# DAQ_Schematic_V1.net
KiCad netlist of a schematic drawn in Altium Designer
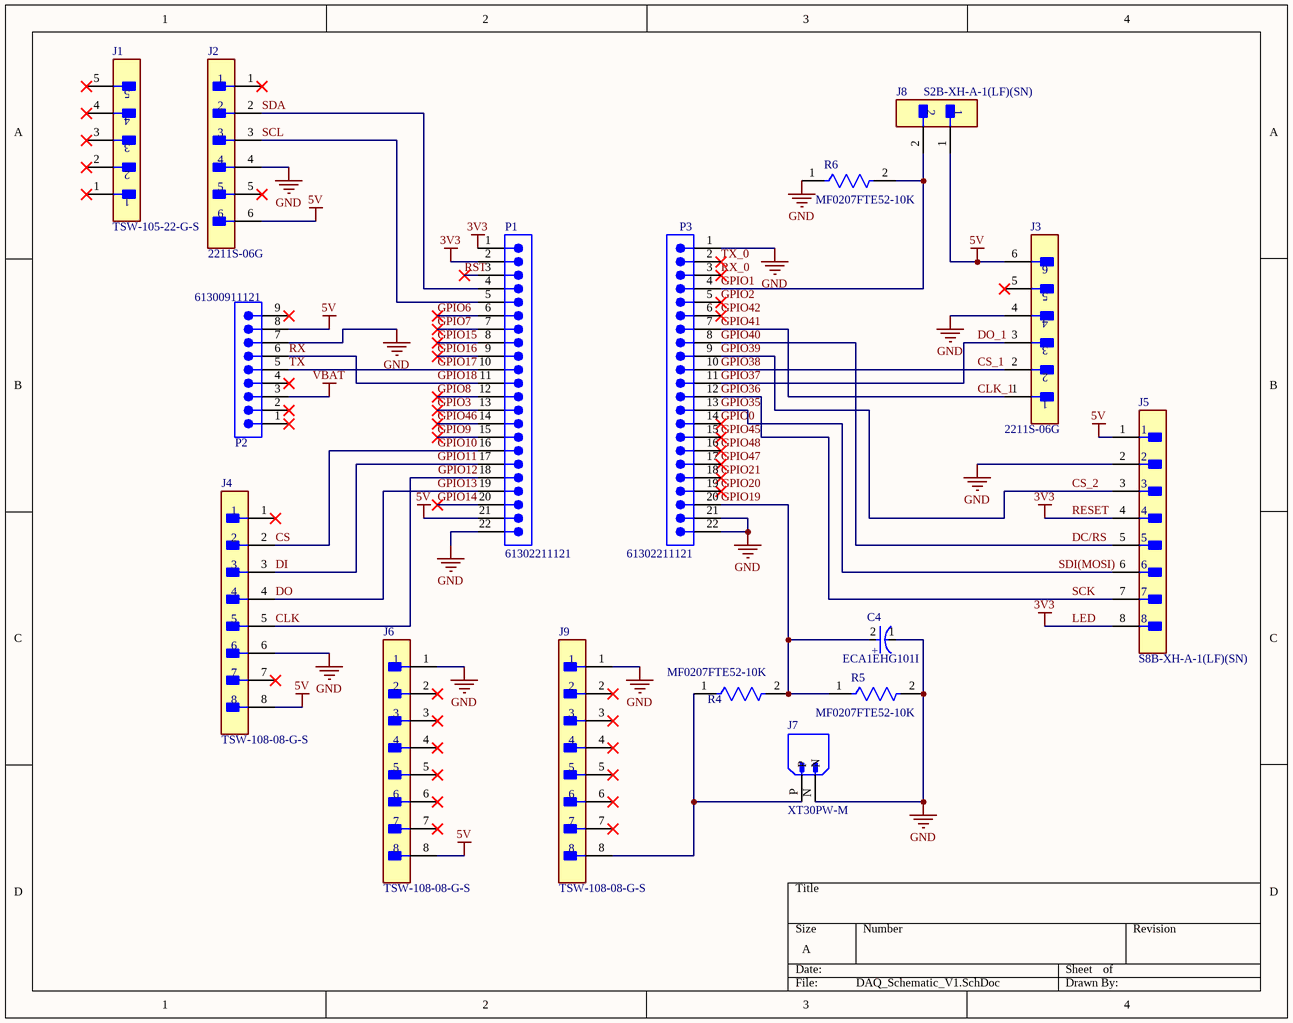
[diagram p0: DAQ_Schematic_V1.SchDoc]

(export (version "E")
  (design (tool "Eeschema 10.0.6"))
  (components
    (comp (ref "C4")
      (value "ECA1EHG101I")
      (footprint "FP-RAD-TH-D_6_3_0_5-L_11-MFG")
      (description "Aluminum Electrolytic Capacitors (Radial Lead Type) AEC-Q200 Qualified 100uF ±20% 25V")
      (fields (field (name "TOLERANCE") "20%"))
      (libsource (lib "Altium Content Vault") (part "203bc49f2ac43e59fd269a8c329ed05"))
    )
    (comp (ref "J1")
      (value "TSW-105-22-G-S")
      (footprint "FP-TSW-105-22-G-S-MFG")
      (description "CONN HEADER VERT 5POS 2.54MM")
      (libsource (lib "Altium Content Vault") (part "bf93c07fd2649a848d0ec8585582aab"))
    )
    (comp (ref "J2")
      (value "2211S-06G")
      (footprint "FP-2211S-06G-MFG")
      (description "Board-To-Board Connector, 2.54 mm, 6 Contacts, Header, 2211S Series, Through Hole, 1 Rows")
      (libsource (lib "") (part "f2cb566baf1c37ab5a3b8e90bbeafd6_1"))
    )
    (comp (ref "J3")
      (value "2211S-06G")
      (footprint "FP-2211S-06G-MFG")
      (description "Board-To-Board Connector, 2.54 mm, 6 Contacts, Header, 2211S Series, Through Hole, 1 Rows")
      (libsource (lib "Altium Content Vault") (part "f2cb566baf1c37ab5a3b8e90bbeafd6"))
    )
    (comp (ref "J4")
      (value "TSW-108-08-G-S")
      (footprint "FP-TSW-108-08-G-S-MFG")
      (description "CONN HEADER VERT 8POS 2.54MM")
      (fields
        (field (name "MANUFACTURER") "Samtec")
        (field (name "OCTOPART") "https://octopart.com/tsw-108-08-g-s-samtec-272653")
      )
      (libsource (lib "") (part "99ec2b232beb5d2356d4d77f6a047f0_1"))
    )
    (comp (ref "J5")
      (value "S8B-XH-A-1(LF)(SN)")
      (footprint "FP-S8B-XH-A-1_LF_SN-MFG")
      (description "CONN HEADER R/A 8POS 2.5MM")
      (libsource (lib "Altium Content Vault") (part "99ec2b232beb5d2356d4d77f6a047f0"))
    )
    (comp (ref "J6")
      (value "TSW-108-08-G-S")
      (footprint "FP-TSW-108-08-G-S-MFG")
      (description "CONN HEADER VERT 8POS 2.54MM")
      (fields
        (field (name "MANUFACTURER") "Samtec")
        (field (name "OCTOPART") "https://octopart.com/tsw-108-08-g-s-samtec-272653")
      )
      (libsource (lib "") (part "99ec2b232beb5d2356d4d77f6a047f0_1"))
    )
    (comp (ref "J7")
      (value "XT30PW-M")
      (footprint "AMASS_XT30PW-M")
      (description "Socket; DC supply; XT30; male; PIN: 2; on PCBs; THT; Colour: yellow")
      (fields (field (name "MF") "AMASS"))
      (libsource (lib "ECE 282 PCB Designs") (part "XT30PW-M"))
    )
    (comp (ref "J8")
      (value "S2B-XH-A-1(LF)(SN)")
      (footprint "FP-S2B-XH-A-1_LF_SN-MFG")
      (description "CONN HEADER R/A 2POS 2.5MM")
      (libsource (lib "Altium Content Vault") (part "3bc925449376181038e59eaffc5286c"))
    )
    (comp (ref "J9")
      (value "TSW-108-08-G-S")
      (footprint "FP-TSW-108-08-G-S-MFG")
      (description "CONN HEADER VERT 8POS 2.54MM")
      (fields
        (field (name "MANUFACTURER") "Samtec")
        (field (name "OCTOPART") "https://octopart.com/tsw-108-08-g-s-samtec-272653")
      )
      (libsource (lib "") (part "99ec2b232beb5d2356d4d77f6a047f0_1"))
    )
    (comp (ref "P1")
      (value "61302211121")
      (footprint "61302211121")
      (description "THT Vertical Pin Header WR-PHD, Pitch 2.54 mm, Single Row, 22 pins")
      (libsource (lib "Altium Content Vault") (part "Header_Male_1R_22P"))
    )
    (comp (ref "P2")
      (value "61300911121")
      (footprint "61300911121")
      (description "THT Vertical Pin Header WR-PHD, Pitch 2.54 mm, Single Row, 9 pins")
      (libsource (lib "Altium Content Vault") (part "Header_Male_1R_09P"))
    )
    (comp (ref "P3")
      (value "61302211121")
      (footprint "61302211121")
      (description "THT Vertical Pin Header WR-PHD, Pitch 2.54 mm, Single Row, 22 pins")
      (libsource (lib "Altium Content Vault") (part "Header_Male_1R_22P"))
    )
    (comp (ref "R4")
      (value "MF0207FTE52-10K")
      (footprint "FP-MF0207-MFG")
      (description "RES 10K OHM 1% 0.6W AXIAL")
      (fields (field (name "TOLERANCE") "1%"))
      (libsource (lib "Altium Content Vault") (part "1029c3af85768c4190bb7ad29bc67b5"))
    )
    (comp (ref "R5")
      (value "MF0207FTE52-10K")
      (footprint "FP-MF0207-MFG")
      (description "RES 10K OHM 1% 0.6W AXIAL")
      (fields (field (name "TOLERANCE") "1%"))
      (libsource (lib "Altium Content Vault") (part "1029c3af85768c4190bb7ad29bc67b5"))
    )
    (comp (ref "R6")
      (value "MF0207FTE52-10K")
      (footprint "FP-MF0207-MFG")
      (description "RES 10K OHM 1% 0.6W AXIAL")
      (fields (field (name "TOLERANCE") "1%"))
      (libsource (lib "Altium Content Vault") (part "1029c3af85768c4190bb7ad29bc67b5"))
    )
  )
  (nets
    (net (code "1") (name "/CLK") (class "Default")
      (node (ref "J4") (pin "5") (pinfunction "5_5") (pintype "passive"))
      (node (ref "P1") (pin "18") (pinfunction "18_18") (pintype "passive"))
    )
    (net (code "2") (name "/CLK_1") (class "Default")
      (node (ref "J3") (pin "1") (pinfunction "1_1") (pintype "passive"))
      (node (ref "P3") (pin "7") (pinfunction "7_7") (pintype "passive"))
    )
    (net (code "3") (name "/CS") (class "Default")
      (node (ref "J4") (pin "2") (pinfunction "2_2") (pintype "passive"))
      (node (ref "P1") (pin "16") (pinfunction "16_16") (pintype "passive"))
    )
    (net (code "4") (name "/CS_1") (class "Default")
      (node (ref "J3") (pin "2") (pinfunction "2_2") (pintype "passive"))
      (node (ref "P3") (pin "10") (pinfunction "10_10") (pintype "passive"))
    )
    (net (code "5") (name "/CS_2") (class "Default")
      (node (ref "J5") (pin "3") (pinfunction "3_3") (pintype "passive"))
      (node (ref "P3") (pin "9") (pinfunction "9_9") (pintype "passive"))
    )
    (net (code "6") (name "/DC{slash}RS") (class "Default")
      (node (ref "J5") (pin "5") (pinfunction "5_5") (pintype "passive"))
      (node (ref "P3") (pin "8") (pinfunction "8_8") (pintype "passive"))
    )
    (net (code "7") (name "/DI") (class "Default")
      (node (ref "J4") (pin "3") (pinfunction "3_3") (pintype "passive"))
      (node (ref "P1") (pin "17") (pinfunction "17_17") (pintype "passive"))
    )
    (net (code "8") (name "/DO") (class "Default")
      (node (ref "J4") (pin "4") (pinfunction "4_4") (pintype "passive"))
      (node (ref "P1") (pin "19") (pinfunction "19_19") (pintype "passive"))
    )
    (net (code "9") (name "/DO_1") (class "Default")
      (node (ref "J3") (pin "3") (pinfunction "3_3") (pintype "passive"))
      (node (ref "P3") (pin "11") (pinfunction "11_11") (pintype "passive"))
    )
    (net (code "10") (name "/GPIO0") (class "Default")
      (node (ref "P3") (pin "14") (pinfunction "14_14") (pintype "passive+no_connect"))
    )
    (net (code "11") (name "/GPIO1") (class "Default")
      (node (ref "J8") (pin "2") (pinfunction "2_2") (pintype "passive"))
      (node (ref "P3") (pin "4") (pinfunction "4_4") (pintype "passive"))
      (node (ref "R6") (pin "2") (pinfunction "2_2") (pintype "passive"))
    )
    (net (code "12") (name "/GPIO2") (class "Default")
      (node (ref "P3") (pin "5") (pinfunction "5_5") (pintype "passive+no_connect"))
    )
    (net (code "13") (name "/GPIO3") (class "Default")
      (node (ref "P1") (pin "13") (pinfunction "13_13") (pintype "passive+no_connect"))
    )
    (net (code "14") (name "/GPIO6") (class "Default")
      (node (ref "P1") (pin "6") (pinfunction "6_6") (pintype "passive+no_connect"))
    )
    (net (code "15") (name "/GPIO7") (class "Default")
      (node (ref "P1") (pin "7") (pinfunction "7_7") (pintype "passive+no_connect"))
    )
    (net (code "16") (name "/GPIO8") (class "Default")
      (node (ref "P1") (pin "12") (pinfunction "12_12") (pintype "passive+no_connect"))
    )
    (net (code "17") (name "/GPIO9") (class "Default")
      (node (ref "P1") (pin "15") (pinfunction "15_15") (pintype "passive+no_connect"))
    )
    (net (code "18") (name "/GPIO14") (class "Default")
      (node (ref "P1") (pin "20") (pinfunction "20_20") (pintype "passive+no_connect"))
    )
    (net (code "19") (name "/GPIO15") (class "Default")
      (node (ref "P1") (pin "8") (pinfunction "8_8") (pintype "passive+no_connect"))
    )
    (net (code "20") (name "/GPIO16") (class "Default")
      (node (ref "P1") (pin "9") (pinfunction "9_9") (pintype "passive+no_connect"))
    )
    (net (code "21") (name "/GPIO17") (class "Default")
      (node (ref "P1") (pin "10") (pinfunction "10_10") (pintype "passive"))
      (node (ref "P2") (pin "5") (pinfunction "5_5") (pintype "passive"))
    )
    (net (code "22") (name "/GPIO18") (class "Default")
      (node (ref "P1") (pin "11") (pinfunction "11_11") (pintype "passive"))
      (node (ref "P2") (pin "6") (pinfunction "6_6") (pintype "passive"))
    )
    (net (code "23") (name "/GPIO19") (class "Default")
      (node (ref "C4") (pin "2") (pinfunction "A_2") (pintype "passive"))
      (node (ref "P3") (pin "20") (pinfunction "20_20") (pintype "passive"))
      (node (ref "R4") (pin "2") (pinfunction "2_2") (pintype "passive"))
      (node (ref "R5") (pin "1") (pinfunction "1_1") (pintype "passive"))
    )
    (net (code "24") (name "/GPIO20") (class "Default")
      (node (ref "P3") (pin "19") (pinfunction "19_19") (pintype "passive+no_connect"))
    )
    (net (code "25") (name "/GPIO21") (class "Default")
      (node (ref "P3") (pin "18") (pinfunction "18_18") (pintype "passive+no_connect"))
    )
    (net (code "26") (name "/GPIO35") (class "Default")
      (node (ref "J5") (pin "6") (pinfunction "6_6") (pintype "passive"))
      (node (ref "P3") (pin "13") (pinfunction "13_13") (pintype "passive"))
    )
    (net (code "27") (name "/GPIO36") (class "Default")
      (node (ref "J5") (pin "7") (pinfunction "7_7") (pintype "passive"))
      (node (ref "P3") (pin "12") (pinfunction "12_12") (pintype "passive"))
    )
    (net (code "28") (name "/GPIO42") (class "Default")
      (node (ref "P3") (pin "6") (pinfunction "6_6") (pintype "passive+no_connect"))
    )
    (net (code "29") (name "/GPIO45") (class "Default")
      (node (ref "P3") (pin "15") (pinfunction "15_15") (pintype "passive+no_connect"))
    )
    (net (code "30") (name "/GPIO46") (class "Default")
      (node (ref "P1") (pin "14") (pinfunction "14_14") (pintype "passive+no_connect"))
    )
    (net (code "31") (name "/GPIO47") (class "Default")
      (node (ref "P3") (pin "17") (pinfunction "17_17") (pintype "passive+no_connect"))
    )
    (net (code "32") (name "/GPIO48") (class "Default")
      (node (ref "P3") (pin "16") (pinfunction "16_16") (pintype "passive+no_connect"))
    )
    (net (code "33") (name "/RST") (class "Default")
      (node (ref "P1") (pin "3") (pinfunction "3_3") (pintype "passive+no_connect"))
    )
    (net (code "34") (name "/RX_0") (class "Default")
      (node (ref "P3") (pin "3") (pinfunction "3_3") (pintype "passive+no_connect"))
    )
    (net (code "35") (name "/SCL") (class "Default")
      (node (ref "J2") (pin "3") (pinfunction "3_3") (pintype "passive"))
      (node (ref "P1") (pin "5") (pinfunction "5_5") (pintype "passive"))
    )
    (net (code "36") (name "/SDA") (class "Default")
      (node (ref "J2") (pin "2") (pinfunction "2_2") (pintype "passive"))
      (node (ref "P1") (pin "4") (pinfunction "4_4") (pintype "passive"))
    )
    (net (code "37") (name "/TX_0") (class "Default")
      (node (ref "P3") (pin "2") (pinfunction "2_2") (pintype "passive+no_connect"))
    )
    (net (code "38") (name "3V3") (class "Default")
      (node (ref "J5") (pin "4") (pinfunction "4_4") (pintype "passive"))
      (node (ref "J5") (pin "8") (pinfunction "8_8") (pintype "passive"))
      (node (ref "P1") (pin "1") (pinfunction "1_1") (pintype "passive"))
      (node (ref "P1") (pin "2") (pinfunction "2_2") (pintype "passive"))
    )
    (net (code "39") (name "5V") (class "Default")
      (node (ref "J2") (pin "6") (pinfunction "6_6") (pintype "passive"))
      (node (ref "J3") (pin "6") (pinfunction "6_6") (pintype "passive"))
      (node (ref "J4") (pin "8") (pinfunction "8_8") (pintype "passive"))
      (node (ref "J5") (pin "1") (pinfunction "1_1") (pintype "passive"))
      (node (ref "J6") (pin "8") (pinfunction "8_8") (pintype "passive"))
      (node (ref "J8") (pin "1") (pinfunction "1_1") (pintype "passive"))
      (node (ref "P1") (pin "21") (pinfunction "21_21") (pintype "passive"))
      (node (ref "P2") (pin "8") (pinfunction "8_8") (pintype "passive"))
    )
    (net (code "40") (name "GND") (class "Default")
      (node (ref "C4") (pin "1") (pinfunction "C_1") (pintype "passive"))
      (node (ref "J2") (pin "4") (pinfunction "4_4") (pintype "passive"))
      (node (ref "J3") (pin "4") (pinfunction "4_4") (pintype "passive"))
      (node (ref "J4") (pin "6") (pinfunction "6_6") (pintype "passive"))
      (node (ref "J5") (pin "2") (pinfunction "2_2") (pintype "passive"))
      (node (ref "J6") (pin "1") (pinfunction "1_1") (pintype "passive"))
      (node (ref "J7") (pin "N") (pinfunction "N_N") (pintype "power_in"))
      (node (ref "J9") (pin "1") (pinfunction "1_1") (pintype "passive"))
      (node (ref "P1") (pin "22") (pinfunction "22_22") (pintype "passive"))
      (node (ref "P2") (pin "7") (pinfunction "7_7") (pintype "passive"))
      (node (ref "P3") (pin "1") (pinfunction "1_1") (pintype "passive"))
      (node (ref "P3") (pin "21") (pinfunction "21_21") (pintype "passive"))
      (node (ref "P3") (pin "22") (pinfunction "22_22") (pintype "passive"))
      (node (ref "R5") (pin "2") (pinfunction "2_2") (pintype "passive"))
      (node (ref "R6") (pin "1") (pinfunction "1_1") (pintype "passive"))
    )
    (net (code "41") (name "Net-(J7-PadP)") (class "Default")
      (node (ref "J7") (pin "P") (pinfunction "P_P") (pintype "power_in"))
      (node (ref "J9") (pin "8") (pinfunction "8_8") (pintype "passive"))
      (node (ref "R4") (pin "1") (pinfunction "1_1") (pintype "passive"))
    )
    (net (code "42") (name "VBAT") (class "Default")
      (node (ref "P2") (pin "3") (pinfunction "3_3") (pintype "passive"))
    )
    (net (code "43") (name "unconnected-(J1-Pad1)") (class "Default")
      (node (ref "J1") (pin "1") (pinfunction "1_1") (pintype "passive+no_connect"))
    )
    (net (code "44") (name "unconnected-(J1-Pad2)") (class "Default")
      (node (ref "J1") (pin "2") (pinfunction "2_2") (pintype "passive+no_connect"))
    )
    (net (code "45") (name "unconnected-(J1-Pad3)") (class "Default")
      (node (ref "J1") (pin "3") (pinfunction "3_3") (pintype "passive+no_connect"))
    )
    (net (code "46") (name "unconnected-(J1-Pad4)") (class "Default")
      (node (ref "J1") (pin "4") (pinfunction "4_4") (pintype "passive+no_connect"))
    )
    (net (code "47") (name "unconnected-(J1-Pad5)") (class "Default")
      (node (ref "J1") (pin "5") (pinfunction "5_5") (pintype "passive+no_connect"))
    )
    (net (code "48") (name "unconnected-(J2-Pad1)") (class "Default")
      (node (ref "J2") (pin "1") (pinfunction "1_1") (pintype "passive+no_connect"))
    )
    (net (code "49") (name "unconnected-(J2-Pad5)") (class "Default")
      (node (ref "J2") (pin "5") (pinfunction "5_5") (pintype "passive+no_connect"))
    )
    (net (code "50") (name "unconnected-(J3-Pad5)") (class "Default")
      (node (ref "J3") (pin "5") (pinfunction "5_5") (pintype "passive+no_connect"))
    )
    (net (code "51") (name "unconnected-(J4-Pad1)") (class "Default")
      (node (ref "J4") (pin "1") (pinfunction "1_1") (pintype "passive+no_connect"))
    )
    (net (code "52") (name "unconnected-(J4-Pad7)") (class "Default")
      (node (ref "J4") (pin "7") (pinfunction "7_7") (pintype "passive+no_connect"))
    )
    (net (code "53") (name "unconnected-(J6-Pad2)") (class "Default")
      (node (ref "J6") (pin "2") (pinfunction "2_2") (pintype "passive+no_connect"))
    )
    (net (code "54") (name "unconnected-(J6-Pad3)") (class "Default")
      (node (ref "J6") (pin "3") (pinfunction "3_3") (pintype "passive+no_connect"))
    )
    (net (code "55") (name "unconnected-(J6-Pad4)") (class "Default")
      (node (ref "J6") (pin "4") (pinfunction "4_4") (pintype "passive+no_connect"))
    )
    (net (code "56") (name "unconnected-(J6-Pad5)") (class "Default")
      (node (ref "J6") (pin "5") (pinfunction "5_5") (pintype "passive+no_connect"))
    )
    (net (code "57") (name "unconnected-(J6-Pad6)") (class "Default")
      (node (ref "J6") (pin "6") (pinfunction "6_6") (pintype "passive+no_connect"))
    )
    (net (code "58") (name "unconnected-(J6-Pad7)") (class "Default")
      (node (ref "J6") (pin "7") (pinfunction "7_7") (pintype "passive+no_connect"))
    )
    (net (code "59") (name "unconnected-(J9-Pad2)") (class "Default")
      (node (ref "J9") (pin "2") (pinfunction "2_2") (pintype "passive+no_connect"))
    )
    (net (code "60") (name "unconnected-(J9-Pad3)") (class "Default")
      (node (ref "J9") (pin "3") (pinfunction "3_3") (pintype "passive+no_connect"))
    )
    (net (code "61") (name "unconnected-(J9-Pad4)") (class "Default")
      (node (ref "J9") (pin "4") (pinfunction "4_4") (pintype "passive+no_connect"))
    )
    (net (code "62") (name "unconnected-(J9-Pad5)") (class "Default")
      (node (ref "J9") (pin "5") (pinfunction "5_5") (pintype "passive+no_connect"))
    )
    (net (code "63") (name "unconnected-(J9-Pad6)") (class "Default")
      (node (ref "J9") (pin "6") (pinfunction "6_6") (pintype "passive+no_connect"))
    )
    (net (code "64") (name "unconnected-(J9-Pad7)") (class "Default")
      (node (ref "J9") (pin "7") (pinfunction "7_7") (pintype "passive+no_connect"))
    )
    (net (code "65") (name "unconnected-(P2-Pad1)") (class "Default")
      (node (ref "P2") (pin "1") (pinfunction "1_1") (pintype "passive+no_connect"))
    )
    (net (code "66") (name "unconnected-(P2-Pad2)") (class "Default")
      (node (ref "P2") (pin "2") (pinfunction "2_2") (pintype "passive+no_connect"))
    )
    (net (code "67") (name "unconnected-(P2-Pad4)") (class "Default")
      (node (ref "P2") (pin "4") (pinfunction "4_4") (pintype "passive+no_connect"))
    )
    (net (code "68") (name "unconnected-(P2-Pad9)") (class "Default")
      (node (ref "P2") (pin "9") (pinfunction "9_9") (pintype "passive+no_connect"))
    )
  )
)
